# sd_shield.net
KiCad netlist of a schematic drawn in EAGLE
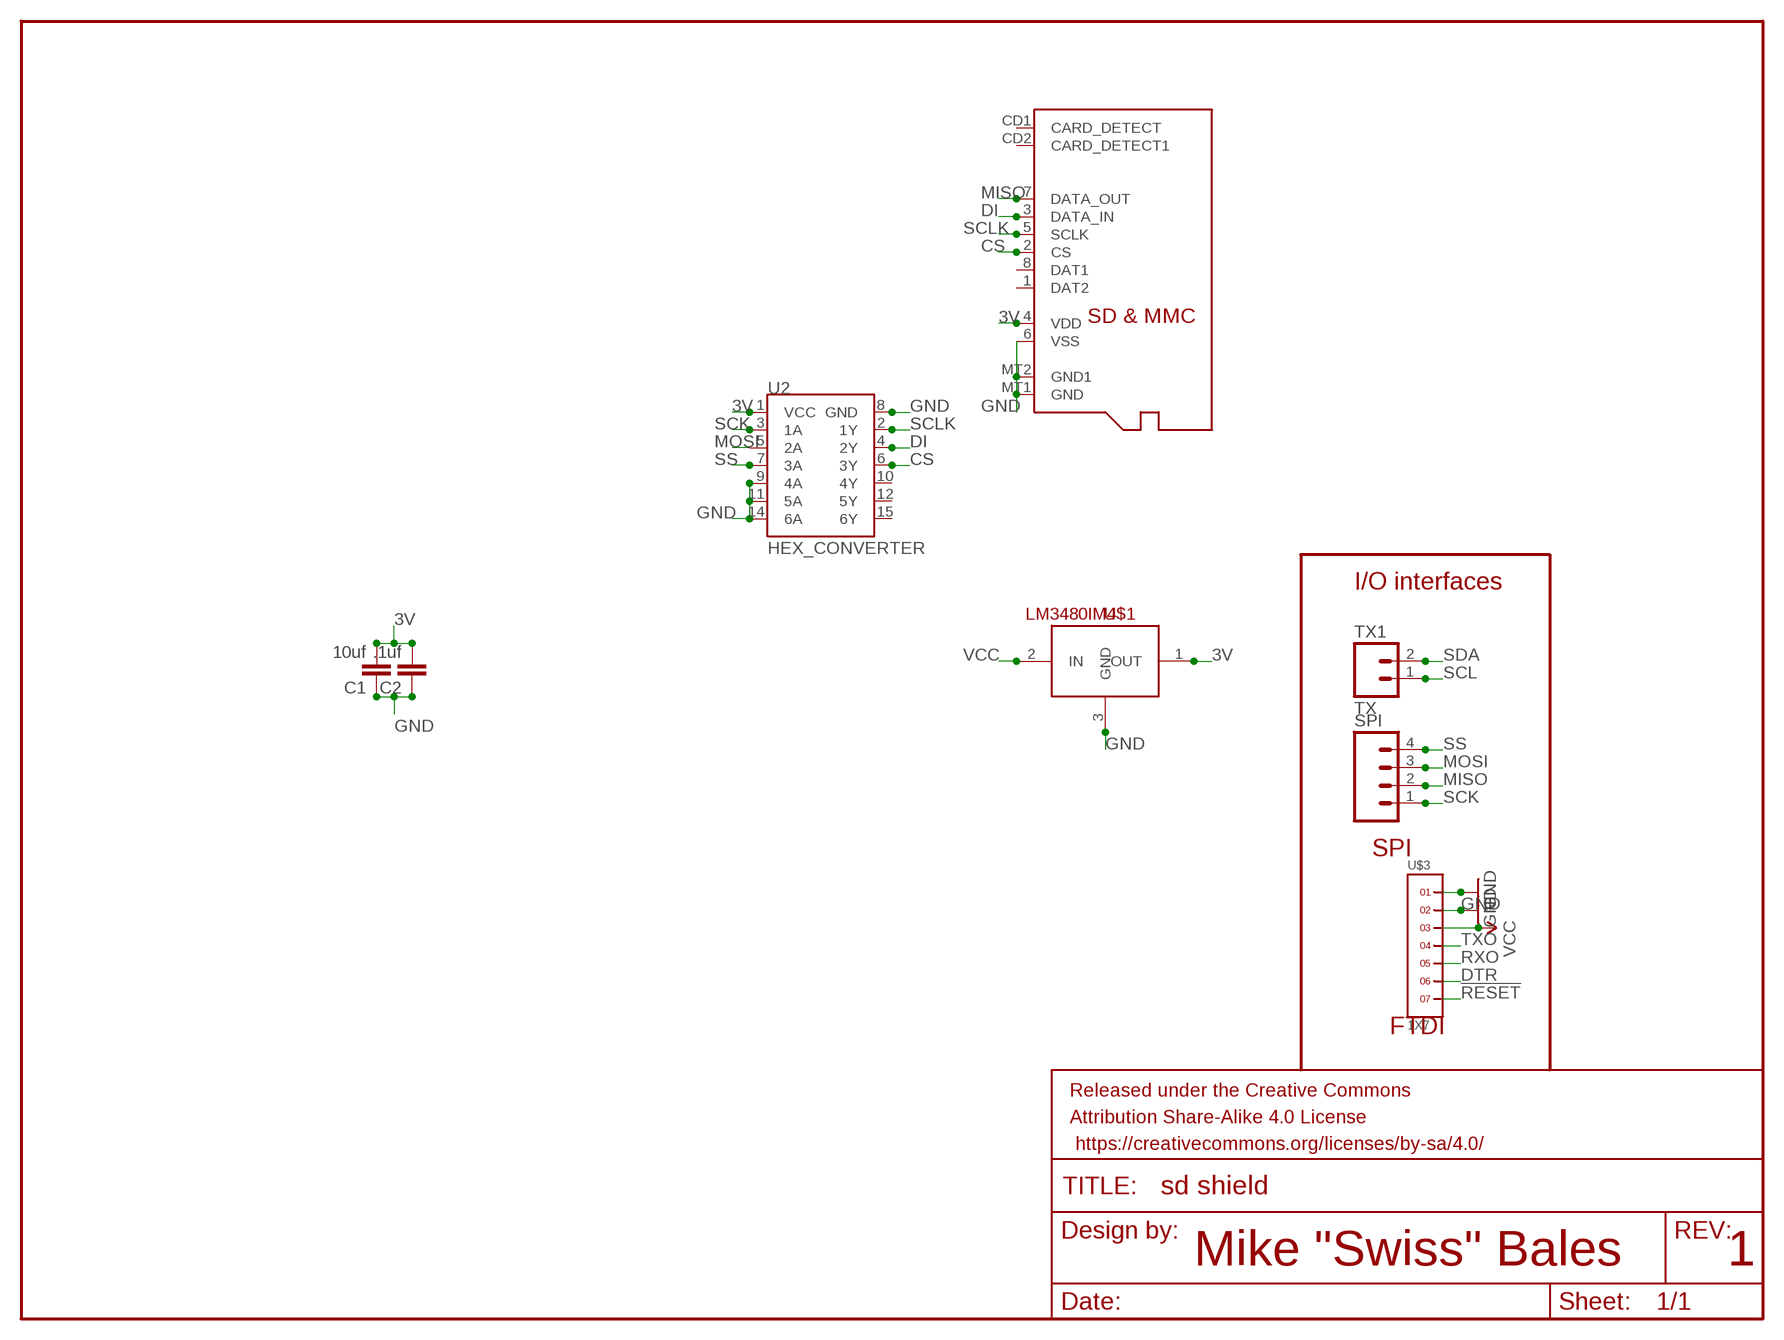
[diagram p0: schematic, sheet 1]

(export (version "E")
  (design (tool "Eeschema 10.0.6"))
  (components
    (comp (ref "C1")
      (value "10uf")
      (footprint "eagle-import:0805")
      (libsource (lib "eagle-import") (part "CAP0805"))
    )
    (comp (ref "C2")
      (value ".1uf")
      (footprint "eagle-import:0805")
      (libsource (lib "eagle-import") (part "CAP0805"))
    )
    (comp (ref "FRAME1")
      (value "FRAME-LETTER")
      (footprint "eagle-import:CREATIVE_COMMONS")
      (libsource (lib "eagle-import") (part "FRAME-LETTER"))
    )
    (comp (ref "SPI")
      (value "M04JST-PTH-VERT")
      (footprint "eagle-import:JST-4-PTH-VERT")
      (libsource (lib "eagle-import") (part "M04JST-PTH-VERT"))
    )
    (comp (ref "TX1")
      (value "TX")
      (footprint "eagle-import:JST-2-PTH-VERT")
      (libsource (lib "eagle-import") (part "M02JST-PTH-VERT"))
    )
    (comp (ref "U$1")
      (value "LM3480IM4")
      (footprint "eagle-import:SOT23-3")
      (libsource (lib "eagle-import") (part "LM3480IM4"))
    )
    (comp (ref "U$2")
      (value "MICROSD")
      (footprint "eagle-import:MICROSD")
      (libsource (lib "eagle-import") (part "MICROSD"))
    )
    (comp (ref "U$3")
      (value "1X7")
      (footprint "eagle-import:1X7")
      (libsource (lib "eagle-import") (part "1X7"))
    )
    (comp (ref "U2")
      (value "HEX_CONVERTER")
      (footprint "eagle-import:SO016")
      (libsource (lib "eagle-import") (part "HEX_CONVERTER"))
    )
  )
  (nets
    (net (code "1") (name "/3V") (class "Default")
      (node (ref "C1") (pin "2") (pinfunction "2_2") (pintype "passive"))
      (node (ref "C2") (pin "2") (pinfunction "2_2") (pintype "passive"))
      (node (ref "U$1") (pin "1") (pinfunction "OUT_1") (pintype "bidirectional"))
      (node (ref "U$2") (pin "4") (pinfunction "VDD_4") (pintype "power_in"))
      (node (ref "U2") (pin "1") (pinfunction "VCC_1") (pintype "bidirectional"))
    )
    (net (code "2") (name "/CS") (class "Default")
      (node (ref "U$2") (pin "2") (pinfunction "CS_2") (pintype "input"))
      (node (ref "U2") (pin "6") (pinfunction "3Y_6") (pintype "bidirectional"))
    )
    (net (code "3") (name "/DI") (class "Default")
      (node (ref "U$2") (pin "3") (pinfunction "DATA_IN_3") (pintype "input"))
      (node (ref "U2") (pin "4") (pinfunction "2Y_4") (pintype "bidirectional"))
    )
    (net (code "4") (name "/DTR") (class "Default")
      (node (ref "U$3") (pin "6") (pinfunction "6_6") (pintype "bidirectional"))
    )
    (net (code "5") (name "/MISO") (class "Default")
      (node (ref "SPI") (pin "2") (pinfunction "2_2") (pintype "passive"))
      (node (ref "U$2") (pin "7") (pinfunction "DATA_OUT_7") (pintype "output"))
    )
    (net (code "6") (name "/MOSI") (class "Default")
      (node (ref "SPI") (pin "3") (pinfunction "3_3") (pintype "passive"))
      (node (ref "U2") (pin "5") (pinfunction "2A_5") (pintype "bidirectional"))
    )
    (net (code "7") (name "/RXO") (class "Default")
      (node (ref "U$3") (pin "5") (pinfunction "5_5") (pintype "bidirectional"))
    )
    (net (code "8") (name "/SCK") (class "Default")
      (node (ref "SPI") (pin "1") (pinfunction "1_1") (pintype "passive"))
      (node (ref "U2") (pin "3") (pinfunction "1A_3") (pintype "bidirectional"))
    )
    (net (code "9") (name "/SCL") (class "Default")
      (node (ref "TX1") (pin "1") (pinfunction "1_1") (pintype "passive"))
    )
    (net (code "10") (name "/SCLK") (class "Default")
      (node (ref "U$2") (pin "5") (pinfunction "SCLK_5") (pintype "input"))
      (node (ref "U2") (pin "2") (pinfunction "1Y_2") (pintype "bidirectional"))
    )
    (net (code "11") (name "/SDA") (class "Default")
      (node (ref "TX1") (pin "2") (pinfunction "2_2") (pintype "passive"))
    )
    (net (code "12") (name "/SS") (class "Default")
      (node (ref "SPI") (pin "4") (pinfunction "4_4") (pintype "passive"))
      (node (ref "U2") (pin "7") (pinfunction "3A_7") (pintype "bidirectional"))
    )
    (net (code "13") (name "/TXO") (class "Default")
      (node (ref "U$3") (pin "4") (pinfunction "4_4") (pintype "bidirectional"))
    )
    (net (code "14") (name "/~{RESET}") (class "Default")
      (node (ref "U$3") (pin "7") (pinfunction "7_7") (pintype "bidirectional"))
    )
    (net (code "15") (name "GND") (class "Default")
      (node (ref "C1") (pin "1") (pinfunction "1_1") (pintype "passive"))
      (node (ref "C2") (pin "1") (pinfunction "1_1") (pintype "passive"))
      (node (ref "U$1") (pin "3") (pinfunction "GND_3") (pintype "bidirectional"))
      (node (ref "U$2") (pin "6") (pinfunction "VSS_6") (pintype "power_in"))
      (node (ref "U$2") (pin "MT1") (pinfunction "GND_MT1") (pintype "power_in"))
      (node (ref "U$2") (pin "MT2") (pinfunction "GND1_MT2") (pintype "power_in"))
      (node (ref "U$3") (pin "1") (pinfunction "1_1") (pintype "bidirectional"))
      (node (ref "U$3") (pin "2") (pinfunction "2_2") (pintype "bidirectional"))
      (node (ref "U2") (pin "11") (pinfunction "5A_11") (pintype "bidirectional"))
      (node (ref "U2") (pin "14") (pinfunction "6A_14") (pintype "bidirectional"))
      (node (ref "U2") (pin "8") (pinfunction "GND_8") (pintype "bidirectional"))
      (node (ref "U2") (pin "9") (pinfunction "4A_9") (pintype "bidirectional"))
    )
    (net (code "16") (name "VCC") (class "Default")
      (node (ref "U$1") (pin "2") (pinfunction "IN_2") (pintype "bidirectional"))
      (node (ref "U$3") (pin "3") (pinfunction "3_3") (pintype "bidirectional"))
    )
    (net (code "17") (name "unconnected-(U$2-CARD_DETECT-PadCD1)") (class "Default")
      (node (ref "U$2") (pin "CD1") (pinfunction "CARD_DETECT_CD1") (pintype "passive"))
    )
    (net (code "18") (name "unconnected-(U$2-CARD_DETECT1-PadCD2)") (class "Default")
      (node (ref "U$2") (pin "CD2") (pinfunction "CARD_DETECT1_CD2") (pintype "passive"))
    )
    (net (code "19") (name "unconnected-(U$2-DAT1-Pad8)") (class "Default")
      (node (ref "U$2") (pin "8") (pinfunction "DAT1_8") (pintype "bidirectional"))
    )
    (net (code "20") (name "unconnected-(U$2-DAT2-Pad1)") (class "Default")
      (node (ref "U$2") (pin "1") (pinfunction "DAT2_1") (pintype "bidirectional"))
    )
    (net (code "21") (name "unconnected-(U2-4Y-Pad10)") (class "Default")
      (node (ref "U2") (pin "10") (pinfunction "4Y_10") (pintype "bidirectional"))
    )
    (net (code "22") (name "unconnected-(U2-5Y-Pad12)") (class "Default")
      (node (ref "U2") (pin "12") (pinfunction "5Y_12") (pintype "bidirectional"))
    )
    (net (code "23") (name "unconnected-(U2-6Y-Pad15)") (class "Default")
      (node (ref "U2") (pin "15") (pinfunction "6Y_15") (pintype "bidirectional"))
    )
  )
)
